# MPPT_V1_0_1_Charger_Converter.net
KiCad netlist of a schematic drawn in Altium Designer
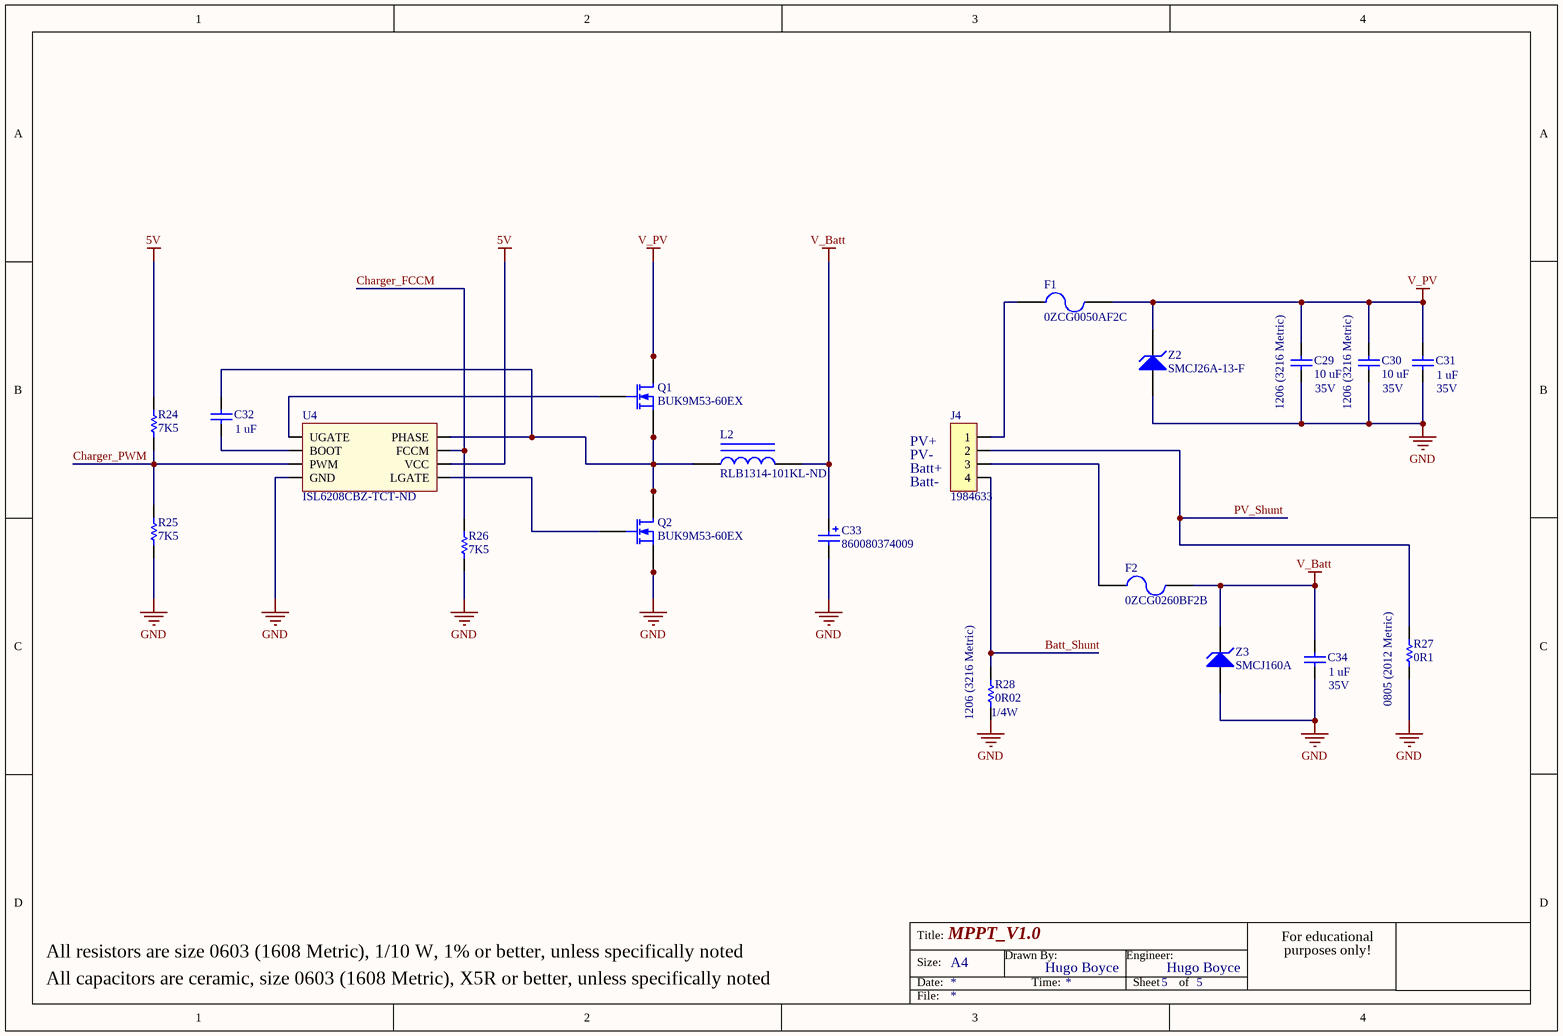
[diagram p0: MPPT_V1.0.1_Charger_Converter.SchDoc]

(export (version "E")
  (design (tool "Eeschema 10.0.6"))
  (components
    (comp (ref "C29")
      (value "10 uF")
      (footprint "CAPC3216N")
      (description "Capacitor")
      (fields
        (field (name "SIZE") "1206 (3216 Metric)")
        (field (name "VOLTAGE RATING") "35V")
        (field (name "Comment") "Cap SMD")
        (field (name "PUBLISHER") "Altium Limited")
      )
      (libsource (lib "Miscellaneous Devices") (part "Cap SMD"))
    )
    (comp (ref "C30")
      (value "10 uF")
      (footprint "CAPC3216N")
      (description "Capacitor")
      (fields
        (field (name "SIZE") "1206 (3216 Metric)")
        (field (name "VOLTAGE RATING") "35V")
        (field (name "Comment") "Cap SMD")
        (field (name "PUBLISHER") "Altium Limited")
      )
      (libsource (lib "Miscellaneous Devices") (part "Cap SMD"))
    )
    (comp (ref "C31")
      (value "1 uF")
      (footprint "CAPC1608N")
      (description "Capacitor")
      (fields
        (field (name "VOLTAGE RATING") "35V")
        (field (name "Comment") "Cap SMD")
        (field (name "PUBLISHER") "Altium Limited")
      )
      (libsource (lib "Miscellaneous Devices") (part "Cap SMD"))
    )
    (comp (ref "C32")
      (value "1 uF")
      (footprint "CAPC1608N")
      (description "Capacitor")
      (fields (field (name "Comment") "Cap SMD") (field (name "PUBLISHER") "Altium Limited"))
      (libsource (lib "Miscellaneous Devices") (part "Cap SMD"))
    )
    (comp (ref "C33")
      (value "860080374009")
      (footprint "860080374009")
      (description "CAP ALUM 220UF 20% 16V THRU HOLE")
      (fields
        (field (name "MANUFACTURER") "Wurth Electronics Inc.")
        (field (name "TOLERANCE") "±20%")
        (field (name "MANUFACTURER PART NUMBER") "860080374009")
      )
      (libsource (lib "MPPT_SCH_Library") (part "860080374009"))
    )
    (comp (ref "C34")
      (value "1 uF")
      (footprint "CAPC1608N")
      (description "Capacitor")
      (fields
        (field (name "VOLTAGE RATING") "35V")
        (field (name "Comment") "Cap SMD")
        (field (name "PUBLISHER") "Altium Limited")
      )
      (libsource (lib "Miscellaneous Devices") (part "Cap SMD"))
    )
    (comp (ref "F1")
      (value "0ZCG0050AF2C")
      (footprint "OZCG0_BEL_FUSE")
      (description "PTC RESET FUSE 30V 500MA 1812")
      (fields
        (field (name "MANUFACTURER") "Bel Fuse Inc.")
        (field (name "MANUFACTURER PART NUMBER") "0ZCG0050AF2C")
      )
      (libsource (lib "MPPT_SCH_Library") (part "0ZCG0050AF2C"))
    )
    (comp (ref "F2")
      (value "0ZCG0260BF2B")
      (footprint "OZCG0_BEL_FUSE")
      (description "PTC RESET FUSE 16V 2.6A 1812")
      (fields
        (field (name "MANUFACTURER") "Bel Fuse Inc.")
        (field (name "MANUFACTURER PART NUMBER") "0ZCG0260BF2B")
      )
      (libsource (lib "MPPT_SCH_Library") (part "0ZCG0260BF2B"))
    )
    (comp (ref "J4")
      (value "1984633")
      (footprint "1984633")
      (description "CONN TERM BLOCK T/H 4POS 3.5MM")
      (fields
        (field (name "MANUFACTURER") "Phoenix Contact")
        (field (name "MANUFACTURER PART NUMBER") "1984633")
      )
      (libsource (lib "MPPT_SCH_Library") (part "1984633"))
    )
    (comp (ref "L2")
      (value "RLB1314-101KL")
      (footprint "BOURNS_RLB1314")
      (description "FIXED IND 100UH 1A 120 MOHM TH")
      (fields
        (field (name "MANUFACTURER") "Bourns Inc.")
        (field (name "TOLERANCE") "±10%")
        (field (name "SUPPLIER PART NUMBER 1") "RLB1314-101KL-ND")
      )
      (libsource (lib "MPPT_SCH_Library") (part "RLB1314-101KL"))
    )
    (comp (ref "Q1")
      (value "BUK9M53-60EX")
      (footprint "BUK9M53-60E")
      (description "MOSFET N-CH 60V 17A LFPAK")
      (fields
        (field (name "MANUFACTURER") "Nexperia USA Inc.")
        (field (name "MANUFACTURER PART NUMBER") "BUK9M53-60EX")
      )
      (libsource (lib "MPPT_SCH_Library") (part "BUK9M53-60EX"))
    )
    (comp (ref "Q2")
      (value "BUK9M53-60EX")
      (footprint "BUK9M53-60E")
      (description "MOSFET N-CH 60V 17A LFPAK")
      (fields
        (field (name "MANUFACTURER") "Nexperia USA Inc.")
        (field (name "MANUFACTURER PART NUMBER") "BUK9M53-60EX")
      )
      (libsource (lib "MPPT_SCH_Library") (part "BUK9M53-60EX"))
    )
    (comp (ref "R24")
      (value "7K5")
      (footprint "RESC1608N")
      (description "Resistor")
      (fields (field (name "Comment") "Res SMD") (field (name "PUBLISHER") "Altium Limited"))
      (libsource (lib "Miscellaneous Devices") (part "Res SMD"))
    )
    (comp (ref "R25")
      (value "7K5")
      (footprint "RESC1608N")
      (description "Resistor")
      (fields (field (name "Comment") "Res SMD") (field (name "PUBLISHER") "Altium Limited"))
      (libsource (lib "Miscellaneous Devices") (part "Res SMD"))
    )
    (comp (ref "R26")
      (value "7K5")
      (footprint "RESC1608N")
      (description "Resistor")
      (fields (field (name "Comment") "Res SMD") (field (name "PUBLISHER") "Altium Limited"))
      (libsource (lib "Miscellaneous Devices") (part "Res SMD"))
    )
    (comp (ref "R27")
      (value "0R1")
      (footprint "RESC2012N")
      (description "Resistor")
      (fields
        (field (name "SIZE") "0805 (2012 Metric)")
        (field (name "Comment") "Res SMD")
        (field (name "PUBLISHER") "Altium Limited")
      )
      (libsource (lib "Miscellaneous Devices") (part "Res SMD"))
    )
    (comp (ref "R28")
      (value "0R02")
      (footprint "RESC3216N")
      (description "Resistor")
      (fields
        (field (name "SIZE") "1206 (3216 Metric)")
        (field (name "POWER RATING") "1/4W")
        (field (name "Comment") "Res SMD")
        (field (name "PUBLISHER") "Altium Limited")
      )
      (libsource (lib "Miscellaneous Devices") (part "Res SMD"))
    )
    (comp (ref "U4")
      (value "ISL6208CBZ-T")
      (footprint "ISL6208CBZ-T")
      (description "IC MOSFET DRVR SYNC BUCK 8-SOIC")
      (fields
        (field (name "MANUFACTURER") "Intersil")
        (field (name "BASE PART NUMBER") "ISL6208")
        (field (name "SUPPLIER PART NUMBER 1") "ISL6208CBZ-TCT-ND")
      )
      (libsource (lib "MPPT_SCH_Library") (part "ISL6208CBZ-T"))
    )
    (comp (ref "Z2")
      (value "SMCJ26A-13-F")
      (footprint "SMCJxxx")
      (description "TVS DIODE 26VWM 42.1VC SMC")
      (fields
        (field (name "MANUFACTURER") "Diodes Incorporated")
        (field (name "BASE PART NUMBER") "SMCJ26")
        (field (name "MANUFACTURER PART NUMBER") "SMCJ26A-13-F")
      )
      (libsource (lib "MPPT_SCH_Library") (part "SMCJ26A-13-F"))
    )
    (comp (ref "Z3")
      (value "SMCJ160A")
      (footprint "SMCJxxx")
      (description "TVS DIODE 160VWM 259VC SMC")
      (fields
        (field (name "MANUFACTURER") "ON Semiconductor")
        (field (name "MANUFACTURER PART NUMBER") "SMCJ160A")
        (field (name "BASE PART NUMBER") "SMCJ160")
      )
      (libsource (lib "MPPT_SCH_Library") (part "SMCJ160A"))
    )
  )
  (nets
    (net (code "1") (name "/Batt_Shunt") (class "Default")
      (node (ref "J4") (pin "4") (pinfunction "4_4") (pintype "passive"))
      (node (ref "R28") (pin "2") (pinfunction "2_2") (pintype "passive"))
    )
    (net (code "2") (name "/Charger_FCCM") (class "Default")
      (node (ref "R26") (pin "2") (pinfunction "2_2") (pintype "passive"))
      (node (ref "U4") (pin "7") (pinfunction "FCCM_7") (pintype "passive"))
    )
    (net (code "3") (name "/Charger_PWM") (class "Default")
      (node (ref "R24") (pin "1") (pinfunction "1_1") (pintype "passive"))
      (node (ref "R25") (pin "2") (pinfunction "2_2") (pintype "passive"))
      (node (ref "U4") (pin "3") (pinfunction "PWM_3") (pintype "passive"))
    )
    (net (code "4") (name "/PV_Shunt") (class "Default")
      (node (ref "J4") (pin "2") (pinfunction "2_2") (pintype "passive"))
      (node (ref "R27") (pin "1") (pinfunction "1_1") (pintype "passive"))
    )
    (net (code "5") (name "5V") (class "Default")
      (node (ref "R24") (pin "2") (pinfunction "2_2") (pintype "passive"))
      (node (ref "U4") (pin "6") (pinfunction "VCC_6") (pintype "passive"))
    )
    (net (code "6") (name "GND") (class "Default")
      (node (ref "C29") (pin "2") (pinfunction "2_2") (pintype "passive"))
      (node (ref "C30") (pin "2") (pinfunction "2_2") (pintype "passive"))
      (node (ref "C31") (pin "1") (pinfunction "1_1") (pintype "passive"))
      (node (ref "C33") (pin "1") (pinfunction "1_1") (pintype "passive"))
      (node (ref "C34") (pin "1") (pinfunction "1_1") (pintype "passive"))
      (node (ref "Q2") (pin "1") (pinfunction "S_1") (pintype "passive"))
      (node (ref "Q2") (pin "2") (pinfunction "S_2") (pintype "passive"))
      (node (ref "Q2") (pin "3") (pinfunction "S_3") (pintype "passive"))
      (node (ref "R25") (pin "1") (pinfunction "1_1") (pintype "passive"))
      (node (ref "R26") (pin "1") (pinfunction "1_1") (pintype "passive"))
      (node (ref "R27") (pin "2") (pinfunction "2_2") (pintype "passive"))
      (node (ref "R28") (pin "1") (pinfunction "1_1") (pintype "passive"))
      (node (ref "U4") (pin "4") (pinfunction "GND_4") (pintype "passive"))
      (node (ref "Z2") (pin "2") (pinfunction "A_2") (pintype "passive"))
      (node (ref "Z3") (pin "2") (pinfunction "A_2") (pintype "passive"))
    )
    (net (code "7") (name "Net-(F1-Pad1)") (class "Default")
      (node (ref "F1") (pin "1") (pinfunction "1_1") (pintype "passive"))
      (node (ref "J4") (pin "1") (pinfunction "1_1") (pintype "passive"))
    )
    (net (code "8") (name "Net-(F2-Pad1)") (class "Default")
      (node (ref "F2") (pin "1") (pinfunction "1_1") (pintype "passive"))
      (node (ref "J4") (pin "3") (pinfunction "3_3") (pintype "passive"))
    )
    (net (code "9") (name "Net-(Q1-G)") (class "Default")
      (node (ref "Q1") (pin "4") (pinfunction "G_4") (pintype "passive"))
      (node (ref "U4") (pin "1") (pinfunction "UGATE_1") (pintype "passive"))
    )
    (net (code "10") (name "Net-(Q2-G)") (class "Default")
      (node (ref "Q2") (pin "4") (pinfunction "G_4") (pintype "passive"))
      (node (ref "U4") (pin "5") (pinfunction "LGATE_5") (pintype "passive"))
    )
    (net (code "11") (name "Net-(U4-BOOT)") (class "Default")
      (node (ref "C32") (pin "1") (pinfunction "1_1") (pintype "passive"))
      (node (ref "U4") (pin "2") (pinfunction "BOOT_2") (pintype "passive"))
    )
    (net (code "12") (name "Net-(U4-PHASE)") (class "Default")
      (node (ref "C32") (pin "2") (pinfunction "2_2") (pintype "passive"))
      (node (ref "L2") (pin "1") (pinfunction "1_1") (pintype "passive"))
      (node (ref "Q1") (pin "1") (pinfunction "S_1") (pintype "passive"))
      (node (ref "Q1") (pin "2") (pinfunction "S_2") (pintype "passive"))
      (node (ref "Q1") (pin "3") (pinfunction "S_3") (pintype "passive"))
      (node (ref "Q2") (pin "5") (pinfunction "D_5") (pintype "passive"))
      (node (ref "Q2") (pin "6") (pinfunction "D_6") (pintype "passive"))
      (node (ref "Q2") (pin "7") (pinfunction "D_7") (pintype "passive"))
      (node (ref "Q2") (pin "8") (pinfunction "D_8") (pintype "passive"))
      (node (ref "U4") (pin "8") (pinfunction "PHASE_8") (pintype "passive"))
    )
    (net (code "13") (name "V_Batt") (class "Default")
      (node (ref "C33") (pin "2") (pinfunction "2_2") (pintype "passive"))
      (node (ref "C34") (pin "2") (pinfunction "2_2") (pintype "passive"))
      (node (ref "F2") (pin "2") (pinfunction "2_2") (pintype "passive"))
      (node (ref "L2") (pin "2") (pinfunction "2_2") (pintype "passive"))
      (node (ref "Z3") (pin "1") (pinfunction "K_1") (pintype "passive"))
    )
    (net (code "14") (name "V_PV") (class "Default")
      (node (ref "C29") (pin "1") (pinfunction "1_1") (pintype "passive"))
      (node (ref "C30") (pin "1") (pinfunction "1_1") (pintype "passive"))
      (node (ref "C31") (pin "2") (pinfunction "2_2") (pintype "passive"))
      (node (ref "F1") (pin "2") (pinfunction "2_2") (pintype "passive"))
      (node (ref "Q1") (pin "5") (pinfunction "D_5") (pintype "passive"))
      (node (ref "Q1") (pin "6") (pinfunction "D_6") (pintype "passive"))
      (node (ref "Q1") (pin "7") (pinfunction "D_7") (pintype "passive"))
      (node (ref "Q1") (pin "8") (pinfunction "D_8") (pintype "passive"))
      (node (ref "Z2") (pin "1") (pinfunction "K_1") (pintype "passive"))
    )
  )
)
